# Quadcopter_Schematic_Final.net
KiCad netlist of a schematic drawn in EAGLE
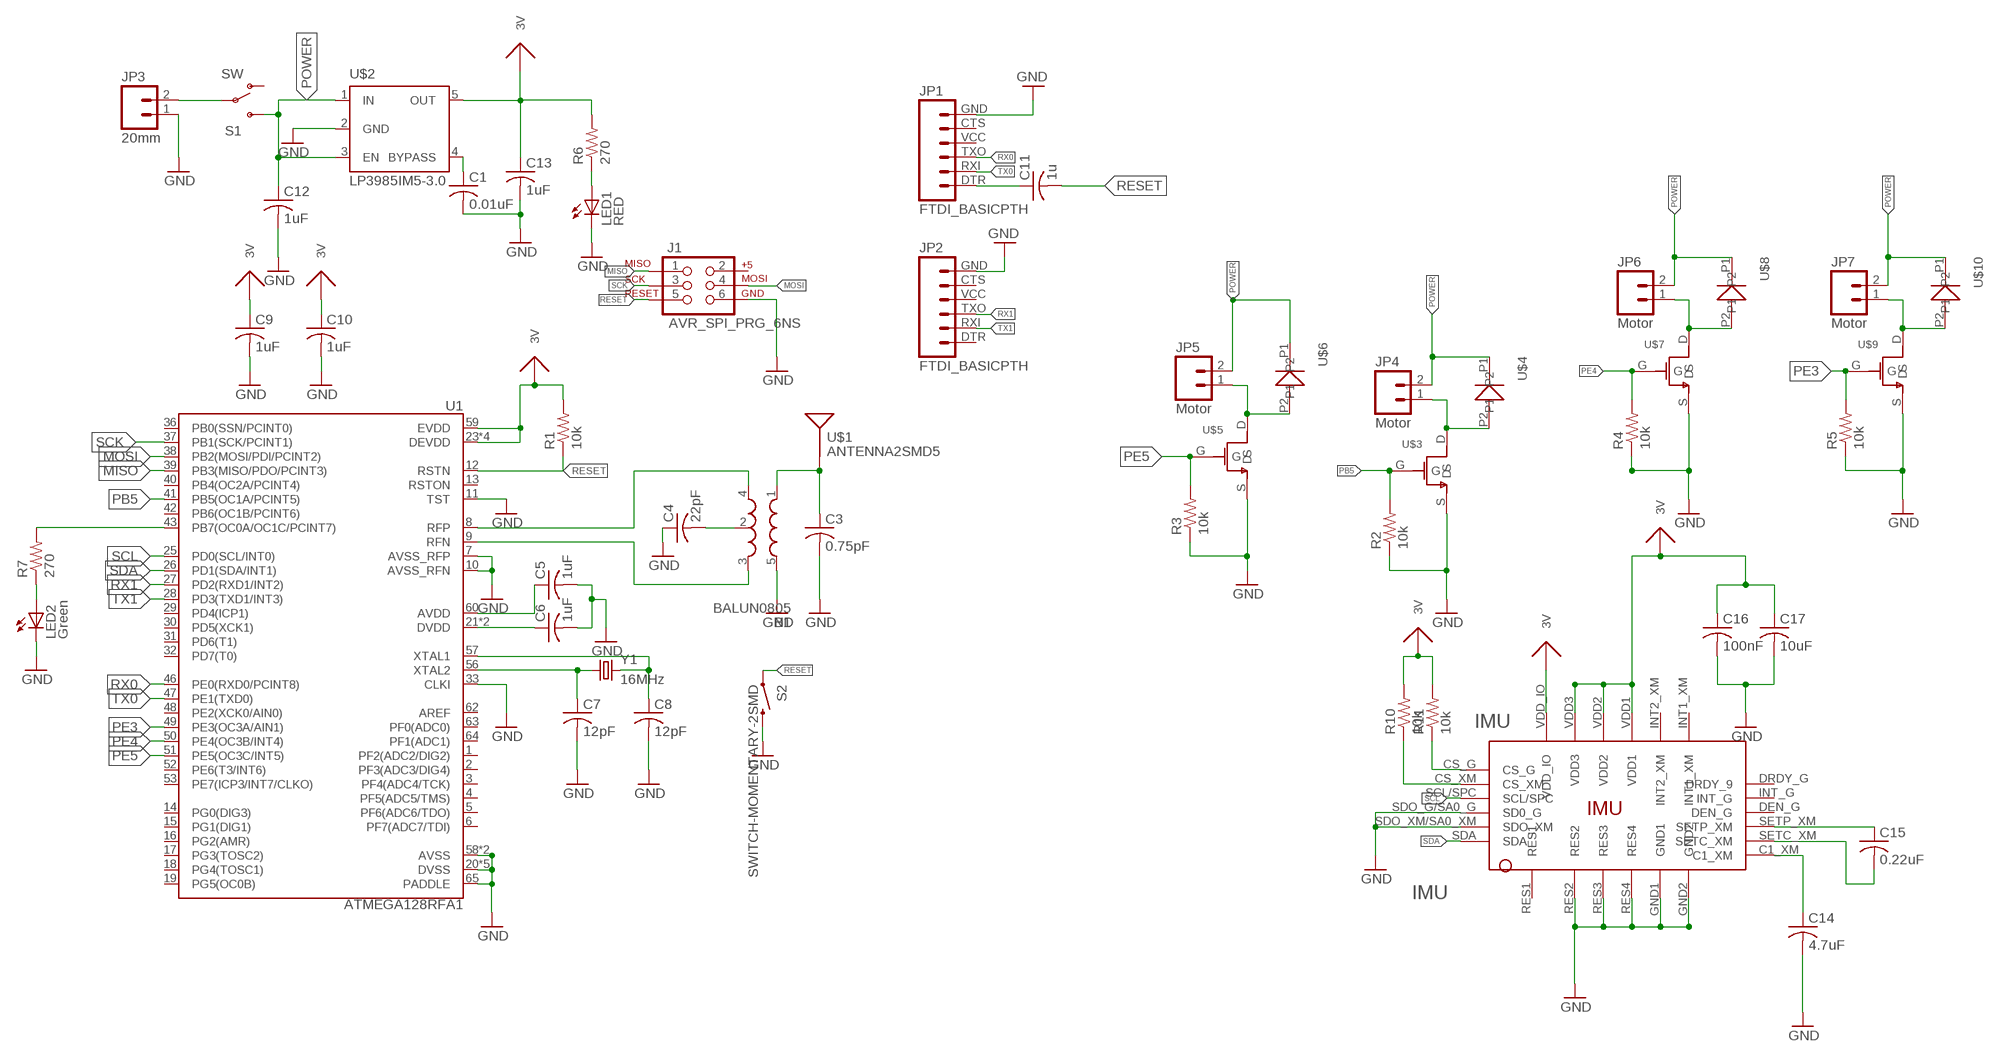
[diagram p0: schematic, sheet 1]

(export (version "E")
  (design (tool "Eeschema 10.0.6"))
  (components
    (comp (ref "B1")
      (value "BALUN0805")
      (footprint "eagle-import:BALUN")
      (libsource (lib "eagle-import") (part "BALUN0805"))
    )
    (comp (ref "C1")
      (value "0.01uF")
      (footprint "eagle-import:C0805")
      (libsource (lib "eagle-import") (part "C-USC0805"))
    )
    (comp (ref "C3")
      (value "0.75pF")
      (footprint "eagle-import:C0805")
      (libsource (lib "eagle-import") (part "C-USC0805"))
    )
    (comp (ref "C4")
      (value "22pF")
      (footprint "eagle-import:C0805")
      (libsource (lib "eagle-import") (part "C-USC0805"))
    )
    (comp (ref "C5")
      (value "1uF")
      (footprint "eagle-import:C0805")
      (libsource (lib "eagle-import") (part "C-USC0805"))
    )
    (comp (ref "C6")
      (value "1uF")
      (footprint "eagle-import:C0805")
      (libsource (lib "eagle-import") (part "C-USC0805"))
    )
    (comp (ref "C7")
      (value "12pF")
      (footprint "eagle-import:C0805")
      (libsource (lib "eagle-import") (part "C-USC0805"))
    )
    (comp (ref "C8")
      (value "12pF")
      (footprint "eagle-import:C0805")
      (libsource (lib "eagle-import") (part "C-USC0805"))
    )
    (comp (ref "C9")
      (value "1uF")
      (footprint "eagle-import:C0805")
      (libsource (lib "eagle-import") (part "C-USC0805"))
    )
    (comp (ref "C10")
      (value "1uF")
      (footprint "eagle-import:C0805")
      (libsource (lib "eagle-import") (part "C-USC0805"))
    )
    (comp (ref "C11")
      (value "1u")
      (footprint "eagle-import:C0805")
      (libsource (lib "eagle-import") (part "C-USC0805"))
    )
    (comp (ref "C12")
      (value "1uF")
      (footprint "eagle-import:C0805")
      (libsource (lib "eagle-import") (part "C-USC0805"))
    )
    (comp (ref "C13")
      (value "1uF")
      (footprint "eagle-import:C0805")
      (libsource (lib "eagle-import") (part "C-USC0805"))
    )
    (comp (ref "C14")
      (value "4.7uF")
      (footprint "eagle-import:C0805")
      (libsource (lib "eagle-import") (part "C-USC0805"))
    )
    (comp (ref "C15")
      (value "0.22uF")
      (footprint "eagle-import:C0805")
      (libsource (lib "eagle-import") (part "C-USC0805"))
    )
    (comp (ref "C16")
      (value "100nF")
      (footprint "eagle-import:C0805")
      (libsource (lib "eagle-import") (part "C-USC0805"))
    )
    (comp (ref "C17")
      (value "10uF")
      (footprint "eagle-import:C0805")
      (libsource (lib "eagle-import") (part "C-USC0805"))
    )
    (comp (ref "IMU")
      (value "IMU")
      (footprint "eagle-import:LSM9DS0")
      (libsource (lib "eagle-import") (part "LSM9DS0"))
    )
    (comp (ref "J1")
      (value "AVR_SPI_PRG_6NS")
      (footprint "eagle-import:2X3-NS")
      (libsource (lib "eagle-import") (part "AVR_SPI_PRG_6NS"))
    )
    (comp (ref "JP1")
      (value "FTDI_BASICPTH")
      (footprint "eagle-import:FTDI_BASIC")
      (libsource (lib "eagle-import") (part "FTDI_BASICPTH"))
    )
    (comp (ref "JP2")
      (value "FTDI_BASICPTH")
      (footprint "eagle-import:FTDI_BASIC")
      (libsource (lib "eagle-import") (part "FTDI_BASICPTH"))
    )
    (comp (ref "JP3")
      (value "20mm")
      (footprint "eagle-import:1X02")
      (libsource (lib "eagle-import") (part "M02PTH"))
    )
    (comp (ref "JP4")
      (value "Motor")
      (footprint "eagle-import:1X02")
      (libsource (lib "eagle-import") (part "M02PTH"))
    )
    (comp (ref "JP5")
      (value "Motor")
      (footprint "eagle-import:1X02")
      (libsource (lib "eagle-import") (part "M02PTH"))
    )
    (comp (ref "JP6")
      (value "Motor")
      (footprint "eagle-import:1X02")
      (libsource (lib "eagle-import") (part "M02PTH"))
    )
    (comp (ref "JP7")
      (value "Motor")
      (footprint "eagle-import:1X02")
      (libsource (lib "eagle-import") (part "M02PTH"))
    )
    (comp (ref "LED1")
      (value "RED")
      (footprint "eagle-import:CHIP-LED0805")
      (libsource (lib "eagle-import") (part "LEDCHIP-LED0805"))
    )
    (comp (ref "LED2")
      (value "Green")
      (footprint "eagle-import:CHIP-LED0805")
      (libsource (lib "eagle-import") (part "LEDCHIP-LED0805"))
    )
    (comp (ref "R1")
      (value "10k")
      (footprint "eagle-import:R0805")
      (libsource (lib "eagle-import") (part "R-US_R0805"))
    )
    (comp (ref "R2")
      (value "10k")
      (footprint "eagle-import:R0805")
      (libsource (lib "eagle-import") (part "R-US_R0805"))
    )
    (comp (ref "R3")
      (value "10k")
      (footprint "eagle-import:R0805")
      (libsource (lib "eagle-import") (part "R-US_R0805"))
    )
    (comp (ref "R4")
      (value "10k")
      (footprint "eagle-import:R0805")
      (libsource (lib "eagle-import") (part "R-US_R0805"))
    )
    (comp (ref "R5")
      (value "10k")
      (footprint "eagle-import:R0805")
      (libsource (lib "eagle-import") (part "R-US_R0805"))
    )
    (comp (ref "R6")
      (value "270")
      (footprint "eagle-import:R0805")
      (libsource (lib "eagle-import") (part "R-US_R0805"))
    )
    (comp (ref "R7")
      (value "270")
      (footprint "eagle-import:R0805")
      (libsource (lib "eagle-import") (part "R-US_R0805"))
    )
    (comp (ref "R10")
      (value "10k")
      (footprint "eagle-import:R0805")
      (libsource (lib "eagle-import") (part "R-US_R0805"))
    )
    (comp (ref "R11")
      (value "10k")
      (footprint "eagle-import:R0805")
      (libsource (lib "eagle-import") (part "R-US_R0805"))
    )
    (comp (ref "S1")
      (value "SW")
      (footprint "eagle-import:SWITCH-SPDT")
      (libsource (lib "eagle-import") (part "SWITCH-SPDTPTH"))
    )
    (comp (ref "S2")
      (value "SWITCH-MOMENTARY-2SMD")
      (footprint "eagle-import:TACTILE_SWITCH_SMD")
      (libsource (lib "eagle-import") (part "SWITCH-MOMENTARY-2SMD"))
    )
    (comp (ref "U$1")
      (value "ANTENNA2SMD5")
      (footprint "eagle-import:ANTENNA-CHIP5")
      (libsource (lib "eagle-import") (part "ANTENNA2SMD5"))
    )
    (comp (ref "U$2")
      (value "LP3985IM5-3.0")
      (footprint "eagle-import:SOT23-DBV")
      (libsource (lib "eagle-import") (part "LP3985IM5-3.0"))
    )
    (comp (ref "U$3")
      (value "NMOS")
      (footprint "eagle-import:SI2302DS_MOSFET")
      (libsource (lib "eagle-import") (part "SI2302DS_MOSFET"))
    )
    (comp (ref "U$4")
      (value "Diode")
      (footprint "eagle-import:BAS16WS_DIODE")
      (libsource (lib "eagle-import") (part "BAS16WS_DIODE"))
    )
    (comp (ref "U$5")
      (value "NMOS")
      (footprint "eagle-import:SI2302DS_MOSFET")
      (libsource (lib "eagle-import") (part "SI2302DS_MOSFET"))
    )
    (comp (ref "U$6")
      (value "Diode")
      (footprint "eagle-import:BAS16WS_DIODE")
      (libsource (lib "eagle-import") (part "BAS16WS_DIODE"))
    )
    (comp (ref "U$7")
      (value "NMOS")
      (footprint "eagle-import:SI2302DS_MOSFET")
      (libsource (lib "eagle-import") (part "SI2302DS_MOSFET"))
    )
    (comp (ref "U$8")
      (value "Diode")
      (footprint "eagle-import:BAS16WS_DIODE")
      (libsource (lib "eagle-import") (part "BAS16WS_DIODE"))
    )
    (comp (ref "U$9")
      (value "NMOS")
      (footprint "eagle-import:SI2302DS_MOSFET")
      (libsource (lib "eagle-import") (part "SI2302DS_MOSFET"))
    )
    (comp (ref "U$10")
      (value "Diode")
      (footprint "eagle-import:BAS16WS_DIODE")
      (libsource (lib "eagle-import") (part "BAS16WS_DIODE"))
    )
    (comp (ref "U1")
      (value "ATMEGA128RFA1")
      (footprint "eagle-import:QFN-64")
      (libsource (lib "eagle-import") (part "ATMEGA128RFA1"))
    )
    (comp (ref "Y1")
      (value "16MHz")
      (footprint "eagle-import:CRYSTAL-SMD-5X3")
      (libsource (lib "eagle-import") (part "CRYSTAL5X3"))
    )
  )
  (nets
    (net (code "1") (name "3V") (class "Default")
      (node (ref "C10") (pin "1") (pinfunction "1_1") (pintype "passive"))
      (node (ref "C13") (pin "1") (pinfunction "1_1") (pintype "passive"))
      (node (ref "C16") (pin "1") (pinfunction "1_1") (pintype "passive"))
      (node (ref "C17") (pin "1") (pinfunction "1_1") (pintype "passive"))
      (node (ref "C9") (pin "1") (pinfunction "1_1") (pintype "passive"))
      (node (ref "IMU") (pin "VDD1") (pinfunction "VDD1_VDD1") (pintype "bidirectional"))
      (node (ref "IMU") (pin "VDD2") (pinfunction "VDD2_VDD2") (pintype "bidirectional"))
      (node (ref "IMU") (pin "VDD3") (pinfunction "VDD3_VDD3") (pintype "bidirectional"))
      (node (ref "IMU") (pin "VDD_IO") (pinfunction "VDD_IO_VDD_IO") (pintype "bidirectional"))
      (node (ref "R1") (pin "2") (pinfunction "2_2") (pintype "passive"))
      (node (ref "R10") (pin "2") (pinfunction "2_2") (pintype "passive"))
      (node (ref "R11") (pin "2") (pinfunction "2_2") (pintype "passive"))
      (node (ref "R6") (pin "2") (pinfunction "2_2") (pintype "passive"))
      (node (ref "U$2") (pin "5") (pinfunction "OUT_5") (pintype "passive"))
      (node (ref "U1") (pin "23") (pinfunction "DEVDD_23") (pintype "bidirectional"))
      (node (ref "U1") (pin "34") (pinfunction "DEVDD_34") (pintype "bidirectional"))
      (node (ref "U1") (pin "44") (pinfunction "DEVDD_44") (pintype "bidirectional"))
      (node (ref "U1") (pin "54") (pinfunction "DEVDD_54") (pintype "bidirectional"))
      (node (ref "U1") (pin "59") (pinfunction "EVDD_59") (pintype "bidirectional"))
    )
    (net (code "2") (name "GND") (class "Default")
      (node (ref "B1") (pin "5") (pinfunction "GND_5") (pintype "bidirectional"))
      (node (ref "C1") (pin "2") (pinfunction "2_2") (pintype "passive"))
      (node (ref "C10") (pin "2") (pinfunction "2_2") (pintype "passive"))
      (node (ref "C12") (pin "2") (pinfunction "2_2") (pintype "passive"))
      (node (ref "C13") (pin "2") (pinfunction "2_2") (pintype "passive"))
      (node (ref "C14") (pin "2") (pinfunction "2_2") (pintype "passive"))
      (node (ref "C16") (pin "2") (pinfunction "2_2") (pintype "passive"))
      (node (ref "C17") (pin "2") (pinfunction "2_2") (pintype "passive"))
      (node (ref "C3") (pin "2") (pinfunction "2_2") (pintype "passive"))
      (node (ref "C4") (pin "1") (pinfunction "1_1") (pintype "passive"))
      (node (ref "C5") (pin "2") (pinfunction "2_2") (pintype "passive"))
      (node (ref "C6") (pin "2") (pinfunction "2_2") (pintype "passive"))
      (node (ref "C7") (pin "2") (pinfunction "2_2") (pintype "passive"))
      (node (ref "C8") (pin "2") (pinfunction "2_2") (pintype "passive"))
      (node (ref "C9") (pin "2") (pinfunction "2_2") (pintype "passive"))
      (node (ref "IMU") (pin "GND1") (pinfunction "GND1_GND1") (pintype "bidirectional"))
      (node (ref "IMU") (pin "GND2") (pinfunction "GND2_GND2") (pintype "bidirectional"))
      (node (ref "IMU") (pin "RES2") (pinfunction "RES2_RES2") (pintype "bidirectional"))
      (node (ref "IMU") (pin "RES3") (pinfunction "RES3_RES3") (pintype "bidirectional"))
      (node (ref "IMU") (pin "RES4") (pinfunction "RES4_RES4") (pintype "bidirectional"))
      (node (ref "IMU") (pin "SDO_G/SA0_G") (pinfunction "SD0_G_SDO_G/SA0_G") (pintype "bidirectional"))
      (node (ref "IMU") (pin "SDO_XM/SA0_XM") (pinfunction "SDO_XM_SDO_XM/SA0_XM") (pintype "bidirectional"))
      (node (ref "J1") (pin "6") (pinfunction "6_6") (pintype "passive"))
      (node (ref "JP1") (pin "GND") (pinfunction "6_GND") (pintype "passive"))
      (node (ref "JP2") (pin "GND") (pinfunction "6_GND") (pintype "passive"))
      (node (ref "JP3") (pin "1") (pinfunction "1_1") (pintype "passive"))
      (node (ref "LED1") (pin "C") (pinfunction "C_C") (pintype "passive"))
      (node (ref "LED2") (pin "C") (pinfunction "C_C") (pintype "passive"))
      (node (ref "R2") (pin "1") (pinfunction "1_1") (pintype "passive"))
      (node (ref "R3") (pin "1") (pinfunction "1_1") (pintype "passive"))
      (node (ref "R4") (pin "1") (pinfunction "1_1") (pintype "passive"))
      (node (ref "R5") (pin "1") (pinfunction "1_1") (pintype "passive"))
      (node (ref "S2") (pin "3") (pinfunction "2_3") (pintype "passive"))
      (node (ref "U$2") (pin "2") (pinfunction "GND_2") (pintype "input"))
      (node (ref "U$3") (pin "S") (pinfunction "S_S") (pintype "bidirectional"))
      (node (ref "U$5") (pin "S") (pinfunction "S_S") (pintype "bidirectional"))
      (node (ref "U$7") (pin "S") (pinfunction "S_S") (pintype "bidirectional"))
      (node (ref "U$9") (pin "S") (pinfunction "S_S") (pintype "bidirectional"))
      (node (ref "U1") (pin "10") (pinfunction "AVSS_RFN_10") (pintype "bidirectional"))
      (node (ref "U1") (pin "11") (pinfunction "TST_11") (pintype "bidirectional"))
      (node (ref "U1") (pin "20") (pinfunction "DVSS_20") (pintype "bidirectional"))
      (node (ref "U1") (pin "24") (pinfunction "DVSS_24") (pintype "bidirectional"))
      (node (ref "U1") (pin "33") (pinfunction "CLKI_33") (pintype "bidirectional"))
      (node (ref "U1") (pin "35") (pinfunction "DVSS_35") (pintype "bidirectional"))
      (node (ref "U1") (pin "45") (pinfunction "DVSS_45") (pintype "bidirectional"))
      (node (ref "U1") (pin "55") (pinfunction "DVSS_55") (pintype "bidirectional"))
      (node (ref "U1") (pin "58") (pinfunction "AVSS_58") (pintype "bidirectional"))
      (node (ref "U1") (pin "61") (pinfunction "AVSS_61") (pintype "bidirectional"))
      (node (ref "U1") (pin "65") (pinfunction "PADDLE_65") (pintype "bidirectional"))
      (node (ref "U1") (pin "7") (pinfunction "AVSS_RFP_7") (pintype "bidirectional"))
    )
    (net (code "3") (name "MISO") (class "Default")
      (node (ref "J1") (pin "1") (pinfunction "1_1") (pintype "passive"))
      (node (ref "U1") (pin "39") (pinfunction "PB3(MISO/PDO/PCINT3)_39") (pintype "bidirectional"))
    )
    (net (code "4") (name "MOSI") (class "Default")
      (node (ref "J1") (pin "4") (pinfunction "4_4") (pintype "passive"))
      (node (ref "U1") (pin "38") (pinfunction "PB2(MOSI/PDI/PCINT2)_38") (pintype "bidirectional"))
    )
    (net (code "5") (name "Net-(B1-GND-Pad2)") (class "Default")
      (node (ref "B1") (pin "2") (pinfunction "GND_2") (pintype "bidirectional"))
      (node (ref "C4") (pin "2") (pinfunction "2_2") (pintype "passive"))
    )
    (net (code "6") (name "Net-(B1-IN)") (class "Default")
      (node (ref "B1") (pin "1") (pinfunction "IN_1") (pintype "bidirectional"))
      (node (ref "C3") (pin "1") (pinfunction "1_1") (pintype "passive"))
      (node (ref "U$1") (pin "FEED") (pinfunction "SIGNAL_FEED") (pintype "bidirectional"))
    )
    (net (code "7") (name "Net-(B1-OUT1)") (class "Default")
      (node (ref "B1") (pin "4") (pinfunction "OUT1_4") (pintype "bidirectional"))
      (node (ref "U1") (pin "8") (pinfunction "RFP_8") (pintype "bidirectional"))
    )
    (net (code "8") (name "Net-(B1-OUT2)") (class "Default")
      (node (ref "B1") (pin "3") (pinfunction "OUT2_3") (pintype "bidirectional"))
      (node (ref "U1") (pin "9") (pinfunction "RFN_9") (pintype "bidirectional"))
    )
    (net (code "9") (name "Net-(C6-Pad1)") (class "Default")
      (node (ref "C6") (pin "1") (pinfunction "1_1") (pintype "passive"))
      (node (ref "U1") (pin "21") (pinfunction "DVDD_21") (pintype "bidirectional"))
      (node (ref "U1") (pin "22") (pinfunction "DVDD_22") (pintype "bidirectional"))
    )
    (net (code "10") (name "Net-(C14-Pad1)") (class "Default")
      (node (ref "C14") (pin "1") (pinfunction "1_1") (pintype "passive"))
      (node (ref "IMU") (pin "C1_XM") (pinfunction "C1_XM_C1_XM") (pintype "bidirectional"))
    )
    (net (code "11") (name "Net-(C15-Pad1)") (class "Default")
      (node (ref "C15") (pin "1") (pinfunction "1_1") (pintype "passive"))
      (node (ref "IMU") (pin "SETP_XM") (pinfunction "SETP_XM_SETP_XM") (pintype "bidirectional"))
    )
    (net (code "12") (name "Net-(C15-Pad2)") (class "Default")
      (node (ref "C15") (pin "2") (pinfunction "2_2") (pintype "passive"))
      (node (ref "IMU") (pin "SETC_XM") (pinfunction "SETC_XM_SETC_XM") (pintype "bidirectional"))
    )
    (net (code "13") (name "Net-(IMU-PadCS_G)") (class "Default")
      (node (ref "IMU") (pin "CS_G") (pinfunction "CS_G_CS_G") (pintype "bidirectional"))
      (node (ref "R11") (pin "1") (pinfunction "1_1") (pintype "passive"))
    )
    (net (code "14") (name "Net-(IMU-PadCS_XM)") (class "Default")
      (node (ref "IMU") (pin "CS_XM") (pinfunction "CS_XM_CS_XM") (pintype "bidirectional"))
      (node (ref "R10") (pin "1") (pinfunction "1_1") (pintype "passive"))
    )
    (net (code "15") (name "Net-(JP1-1)") (class "Default")
      (node (ref "C11") (pin "1") (pinfunction "1_1") (pintype "passive"))
      (node (ref "JP1") (pin "DTR") (pinfunction "1_DTR") (pintype "passive"))
    )
    (net (code "16") (name "Net-(JP4-Pad1)") (class "Default")
      (node (ref "JP4") (pin "1") (pinfunction "1_1") (pintype "passive"))
      (node (ref "U$3") (pin "D") (pinfunction "D_D") (pintype "bidirectional"))
      (node (ref "U$4") (pin "P2") (pinfunction "P2_P2") (pintype "bidirectional"))
    )
    (net (code "17") (name "Net-(JP5-Pad1)") (class "Default")
      (node (ref "JP5") (pin "1") (pinfunction "1_1") (pintype "passive"))
      (node (ref "U$5") (pin "D") (pinfunction "D_D") (pintype "bidirectional"))
      (node (ref "U$6") (pin "P2") (pinfunction "P2_P2") (pintype "bidirectional"))
    )
    (net (code "18") (name "Net-(JP6-Pad1)") (class "Default")
      (node (ref "JP6") (pin "1") (pinfunction "1_1") (pintype "passive"))
      (node (ref "U$7") (pin "D") (pinfunction "D_D") (pintype "bidirectional"))
      (node (ref "U$8") (pin "P2") (pinfunction "P2_P2") (pintype "bidirectional"))
    )
    (net (code "19") (name "Net-(JP7-Pad1)") (class "Default")
      (node (ref "JP7") (pin "1") (pinfunction "1_1") (pintype "passive"))
      (node (ref "U$10") (pin "P2") (pinfunction "P2_P2") (pintype "bidirectional"))
      (node (ref "U$9") (pin "D") (pinfunction "D_D") (pintype "bidirectional"))
    )
    (net (code "20") (name "Net-(LED1-PadA)") (class "Default")
      (node (ref "LED1") (pin "A") (pinfunction "A_A") (pintype "passive"))
      (node (ref "R6") (pin "1") (pinfunction "1_1") (pintype "passive"))
    )
    (net (code "21") (name "Net-(LED2-PadA)") (class "Default")
      (node (ref "LED2") (pin "A") (pinfunction "A_A") (pintype "passive"))
      (node (ref "R7") (pin "1") (pinfunction "1_1") (pintype "passive"))
    )
    (net (code "22") (name "Net-(S1-P)") (class "Default")
      (node (ref "JP3") (pin "2") (pinfunction "2_2") (pintype "passive"))
      (node (ref "S1") (pin "2") (pinfunction "P_2") (pintype "passive"))
    )
    (net (code "23") (name "Net-(U$2-BYPASS)") (class "Default")
      (node (ref "C1") (pin "1") (pinfunction "1_1") (pintype "passive"))
      (node (ref "U$2") (pin "4") (pinfunction "BYPASS_4") (pintype "passive"))
    )
    (net (code "24") (name "Net-(U1-AVDD)") (class "Default")
      (node (ref "C5") (pin "1") (pinfunction "1_1") (pintype "passive"))
      (node (ref "U1") (pin "60") (pinfunction "AVDD_60") (pintype "bidirectional"))
    )
    (net (code "25") (name "Net-(U1-PB7(OC0A{slash}OC1C{slash}PCINT7))") (class "Default")
      (node (ref "R7") (pin "2") (pinfunction "2_2") (pintype "passive"))
      (node (ref "U1") (pin "43") (pinfunction "PB7(OC0A/OC1C/PCINT7)_43") (pintype "bidirectional"))
    )
    (net (code "26") (name "Net-(U1-XTAL1)") (class "Default")
      (node (ref "C8") (pin "1") (pinfunction "1_1") (pintype "passive"))
      (node (ref "U1") (pin "57") (pinfunction "XTAL1_57") (pintype "bidirectional"))
      (node (ref "Y1") (pin "3") (pinfunction "2_3") (pintype "passive"))
    )
    (net (code "27") (name "Net-(U1-XTAL2)") (class "Default")
      (node (ref "C7") (pin "1") (pinfunction "1_1") (pintype "passive"))
      (node (ref "U1") (pin "56") (pinfunction "XTAL2_56") (pintype "bidirectional"))
      (node (ref "Y1") (pin "1") (pinfunction "1_1") (pintype "passive"))
    )
    (net (code "28") (name "PB5") (class "Default")
      (node (ref "R2") (pin "2") (pinfunction "2_2") (pintype "passive"))
      (node (ref "U$3") (pin "G") (pinfunction "G_G") (pintype "bidirectional"))
      (node (ref "U1") (pin "41") (pinfunction "PB5(OC1A/PCINT5)_41") (pintype "bidirectional"))
    )
    (net (code "29") (name "PE3") (class "Default")
      (node (ref "R5") (pin "2") (pinfunction "2_2") (pintype "passive"))
      (node (ref "U$9") (pin "G") (pinfunction "G_G") (pintype "bidirectional"))
      (node (ref "U1") (pin "49") (pinfunction "PE3(OC3A/AIN1)_49") (pintype "bidirectional"))
    )
    (net (code "30") (name "PE4") (class "Default")
      (node (ref "R4") (pin "2") (pinfunction "2_2") (pintype "passive"))
      (node (ref "U$7") (pin "G") (pinfunction "G_G") (pintype "bidirectional"))
      (node (ref "U1") (pin "50") (pinfunction "PE4(OC3B/INT4)_50") (pintype "bidirectional"))
    )
    (net (code "31") (name "PE5") (class "Default")
      (node (ref "R3") (pin "2") (pinfunction "2_2") (pintype "passive"))
      (node (ref "U$5") (pin "G") (pinfunction "G_G") (pintype "bidirectional"))
      (node (ref "U1") (pin "51") (pinfunction "PE5(OC3C/INT5)_51") (pintype "bidirectional"))
    )
    (net (code "32") (name "POWER") (class "Default")
      (node (ref "C12") (pin "1") (pinfunction "1_1") (pintype "passive"))
      (node (ref "JP4") (pin "2") (pinfunction "2_2") (pintype "passive"))
      (node (ref "JP5") (pin "2") (pinfunction "2_2") (pintype "passive"))
      (node (ref "JP6") (pin "2") (pinfunction "2_2") (pintype "passive"))
      (node (ref "JP7") (pin "2") (pinfunction "2_2") (pintype "passive"))
      (node (ref "S1") (pin "3") (pinfunction "S_3") (pintype "passive"))
      (node (ref "U$10") (pin "P1") (pinfunction "P1_P1") (pintype "bidirectional"))
      (node (ref "U$2") (pin "1") (pinfunction "IN_1") (pintype "input"))
      (node (ref "U$2") (pin "3") (pinfunction "EN_3") (pintype "bidirectional"))
      (node (ref "U$4") (pin "P1") (pinfunction "P1_P1") (pintype "bidirectional"))
      (node (ref "U$6") (pin "P1") (pinfunction "P1_P1") (pintype "bidirectional"))
      (node (ref "U$8") (pin "P1") (pinfunction "P1_P1") (pintype "bidirectional"))
    )
    (net (code "33") (name "RESET") (class "Default")
      (node (ref "C11") (pin "2") (pinfunction "2_2") (pintype "passive"))
      (node (ref "J1") (pin "5") (pinfunction "5_5") (pintype "passive"))
      (node (ref "R1") (pin "1") (pinfunction "1_1") (pintype "passive"))
      (node (ref "S2") (pin "1") (pinfunction "1_1") (pintype "passive"))
      (node (ref "U1") (pin "12") (pinfunction "RSTN_12") (pintype "bidirectional"))
    )
    (net (code "34") (name "RX0") (class "Default")
      (node (ref "JP1") (pin "TXO") (pinfunction "3_TXO") (pintype "passive"))
      (node (ref "U1") (pin "46") (pinfunction "PE0(RXD0/PCINT8)_46") (pintype "bidirectional"))
    )
    (net (code "35") (name "RX1") (class "Default")
      (node (ref "JP2") (pin "TXO") (pinfunction "3_TXO") (pintype "passive"))
      (node (ref "U1") (pin "27") (pinfunction "PD2(RXD1/INT2)_27") (pintype "bidirectional"))
    )
    (net (code "36") (name "SCK") (class "Default")
      (node (ref "J1") (pin "3") (pinfunction "3_3") (pintype "passive"))
      (node (ref "U1") (pin "37") (pinfunction "PB1(SCK/PCINT1)_37") (pintype "bidirectional"))
    )
    (net (code "37") (name "SCL") (class "Default")
      (node (ref "IMU") (pin "SCL/SPC") (pinfunction "SCL/SPC_SCL/SPC") (pintype "bidirectional"))
      (node (ref "U1") (pin "25") (pinfunction "PD0(SCL/INT0)_25") (pintype "bidirectional"))
    )
    (net (code "38") (name "SDA") (class "Default")
      (node (ref "IMU") (pin "SDA") (pinfunction "SDA_SDA") (pintype "bidirectional"))
      (node (ref "U1") (pin "26") (pinfunction "PD1(SDA/INT1)_26") (pintype "bidirectional"))
    )
    (net (code "39") (name "TX0") (class "Default")
      (node (ref "JP1") (pin "RXI") (pinfunction "2_RXI") (pintype "passive"))
      (node (ref "U1") (pin "47") (pinfunction "PE1(TXD0)_47") (pintype "bidirectional"))
    )
    (net (code "40") (name "TX1") (class "Default")
      (node (ref "JP2") (pin "RXI") (pinfunction "2_RXI") (pintype "passive"))
      (node (ref "U1") (pin "28") (pinfunction "PD3(TXD1/INT3)_28") (pintype "bidirectional"))
    )
    (net (code "41") (name "unconnected-(IMU-DRDY_9-PadDRDY_G)") (class "Default")
      (node (ref "IMU") (pin "DRDY_G") (pinfunction "DRDY_9_DRDY_G") (pintype "bidirectional"))
    )
    (net (code "42") (name "unconnected-(IMU-PadDEN_G)") (class "Default")
      (node (ref "IMU") (pin "DEN_G") (pinfunction "DEN_G_DEN_G") (pintype "bidirectional"))
    )
    (net (code "43") (name "unconnected-(IMU-PadINT1_XM)") (class "Default")
      (node (ref "IMU") (pin "INT1_XM") (pinfunction "INT1_XM_INT1_XM") (pintype "bidirectional"))
    )
    (net (code "44") (name "unconnected-(IMU-PadINT2_XM)") (class "Default")
      (node (ref "IMU") (pin "INT2_XM") (pinfunction "INT2_XM_INT2_XM") (pintype "bidirectional"))
    )
    (net (code "45") (name "unconnected-(IMU-PadINT_G)") (class "Default")
      (node (ref "IMU") (pin "INT_G") (pinfunction "INT_G_INT_G") (pintype "bidirectional"))
    )
    (net (code "46") (name "unconnected-(IMU-PadRES1)") (class "Default")
      (node (ref "IMU") (pin "RES1") (pinfunction "RES1_RES1") (pintype "bidirectional"))
    )
    (net (code "47") (name "unconnected-(J1-Pad2)") (class "Default")
      (node (ref "J1") (pin "2") (pinfunction "2_2") (pintype "passive"))
    )
    (net (code "48") (name "unconnected-(JP1-4-PadVCC)") (class "Default")
      (node (ref "JP1") (pin "VCC") (pinfunction "4_VCC") (pintype "passive"))
    )
    (net (code "49") (name "unconnected-(JP1-5-PadCTS)") (class "Default")
      (node (ref "JP1") (pin "CTS") (pinfunction "5_CTS") (pintype "passive"))
    )
    (net (code "50") (name "unconnected-(JP2-1-PadDTR)") (class "Default")
      (node (ref "JP2") (pin "DTR") (pinfunction "1_DTR") (pintype "passive"))
    )
    (net (code "51") (name "unconnected-(JP2-4-PadVCC)") (class "Default")
      (node (ref "JP2") (pin "VCC") (pinfunction "4_VCC") (pintype "passive"))
    )
    (net (code "52") (name "unconnected-(JP2-5-PadCTS)") (class "Default")
      (node (ref "JP2") (pin "CTS") (pinfunction "5_CTS") (pintype "passive"))
    )
    (net (code "53") (name "unconnected-(S1-O-Pad1)") (class "Default")
      (node (ref "S1") (pin "1") (pinfunction "O_1") (pintype "passive"))
    )
    (net (code "54") (name "unconnected-(U1-AREF-Pad62)") (class "Default")
      (node (ref "U1") (pin "62") (pinfunction "AREF_62") (pintype "bidirectional"))
    )
    (net (code "55") (name "unconnected-(U1-PB0(SSN{slash}PCINT0)-Pad36)") (class "Default")
      (node (ref "U1") (pin "36") (pinfunction "PB0(SSN/PCINT0)_36") (pintype "bidirectional"))
    )
    (net (code "56") (name "unconnected-(U1-PB4(OC2A{slash}PCINT4)-Pad40)") (class "Default")
      (node (ref "U1") (pin "40") (pinfunction "PB4(OC2A/PCINT4)_40") (pintype "bidirectional"))
    )
    (net (code "57") (name "unconnected-(U1-PB6(OC1B{slash}PCINT6)-Pad42)") (class "Default")
      (node (ref "U1") (pin "42") (pinfunction "PB6(OC1B/PCINT6)_42") (pintype "bidirectional"))
    )
    (net (code "58") (name "unconnected-(U1-PD4(ICP1)-Pad29)") (class "Default")
      (node (ref "U1") (pin "29") (pinfunction "PD4(ICP1)_29") (pintype "bidirectional"))
    )
    (net (code "59") (name "unconnected-(U1-PD5(XCK1)-Pad30)") (class "Default")
      (node (ref "U1") (pin "30") (pinfunction "PD5(XCK1)_30") (pintype "bidirectional"))
    )
    (net (code "60") (name "unconnected-(U1-PD6(T1)-Pad31)") (class "Default")
      (node (ref "U1") (pin "31") (pinfunction "PD6(T1)_31") (pintype "bidirectional"))
    )
    (net (code "61") (name "unconnected-(U1-PD7(T0)-Pad32)") (class "Default")
      (node (ref "U1") (pin "32") (pinfunction "PD7(T0)_32") (pintype "bidirectional"))
    )
    (net (code "62") (name "unconnected-(U1-PE2(XCK0{slash}AIN0)-Pad48)") (class "Default")
      (node (ref "U1") (pin "48") (pinfunction "PE2(XCK0/AIN0)_48") (pintype "bidirectional"))
    )
    (net (code "63") (name "unconnected-(U1-PE6(T3{slash}INT6)-Pad52)") (class "Default")
      (node (ref "U1") (pin "52") (pinfunction "PE6(T3/INT6)_52") (pintype "bidirectional"))
    )
    (net (code "64") (name "unconnected-(U1-PE7(ICP3{slash}INT7{slash}CLKO)-Pad53)") (class "Default")
      (node (ref "U1") (pin "53") (pinfunction "PE7(ICP3/INT7/CLKO)_53") (pintype "bidirectional"))
    )
    (net (code "65") (name "unconnected-(U1-PF0(ADC0)-Pad63)") (class "Default")
      (node (ref "U1") (pin "63") (pinfunction "PF0(ADC0)_63") (pintype "bidirectional"))
    )
    (net (code "66") (name "unconnected-(U1-PF1(ADC1)-Pad64)") (class "Default")
      (node (ref "U1") (pin "64") (pinfunction "PF1(ADC1)_64") (pintype "bidirectional"))
    )
    (net (code "67") (name "unconnected-(U1-PF2(ADC2{slash}DIG2)-Pad1)") (class "Default")
      (node (ref "U1") (pin "1") (pinfunction "PF2(ADC2/DIG2)_1") (pintype "bidirectional"))
    )
    (net (code "68") (name "unconnected-(U1-PF3(ADC3{slash}DIG4)-Pad2)") (class "Default")
      (node (ref "U1") (pin "2") (pinfunction "PF3(ADC3/DIG4)_2") (pintype "bidirectional"))
    )
    (net (code "69") (name "unconnected-(U1-PF4(ADC4{slash}TCK)-Pad3)") (class "Default")
      (node (ref "U1") (pin "3") (pinfunction "PF4(ADC4/TCK)_3") (pintype "bidirectional"))
    )
    (net (code "70") (name "unconnected-(U1-PF5(ADC5{slash}TMS)-Pad4)") (class "Default")
      (node (ref "U1") (pin "4") (pinfunction "PF5(ADC5/TMS)_4") (pintype "bidirectional"))
    )
    (net (code "71") (name "unconnected-(U1-PF6(ADC6{slash}TDO)-Pad5)") (class "Default")
      (node (ref "U1") (pin "5") (pinfunction "PF6(ADC6/TDO)_5") (pintype "bidirectional"))
    )
    (net (code "72") (name "unconnected-(U1-PF7(ADC7{slash}TDI)-Pad6)") (class "Default")
      (node (ref "U1") (pin "6") (pinfunction "PF7(ADC7/TDI)_6") (pintype "bidirectional"))
    )
    (net (code "73") (name "unconnected-(U1-PG0(DIG3)-Pad14)") (class "Default")
      (node (ref "U1") (pin "14") (pinfunction "PG0(DIG3)_14") (pintype "bidirectional"))
    )
    (net (code "74") (name "unconnected-(U1-PG1(DIG1)-Pad15)") (class "Default")
      (node (ref "U1") (pin "15") (pinfunction "PG1(DIG1)_15") (pintype "bidirectional"))
    )
    (net (code "75") (name "unconnected-(U1-PG2(AMR)-Pad16)") (class "Default")
      (node (ref "U1") (pin "16") (pinfunction "PG2(AMR)_16") (pintype "bidirectional"))
    )
    (net (code "76") (name "unconnected-(U1-PG3(TOSC2)-Pad17)") (class "Default")
      (node (ref "U1") (pin "17") (pinfunction "PG3(TOSC2)_17") (pintype "bidirectional"))
    )
    (net (code "77") (name "unconnected-(U1-PG4(TOSC1)-Pad18)") (class "Default")
      (node (ref "U1") (pin "18") (pinfunction "PG4(TOSC1)_18") (pintype "bidirectional"))
    )
    (net (code "78") (name "unconnected-(U1-PG5(OC0B)-Pad19)") (class "Default")
      (node (ref "U1") (pin "19") (pinfunction "PG5(OC0B)_19") (pintype "bidirectional"))
    )
    (net (code "79") (name "unconnected-(U1-RSTON-Pad13)") (class "Default")
      (node (ref "U1") (pin "13") (pinfunction "RSTON_13") (pintype "bidirectional"))
    )
  )
)
